# Sheet5.net
KiCad netlist of a schematic drawn in Altium Designer
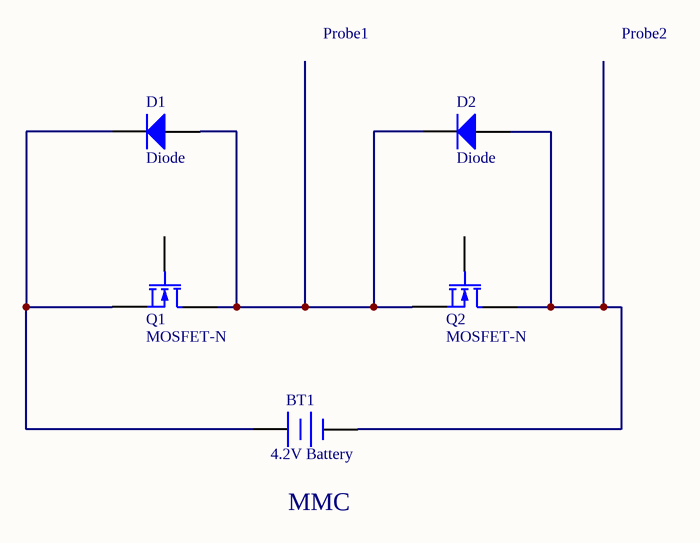
[diagram p0: Sheet5.SchDoc]

(export (version "E")
  (design (tool "Eeschema 10.0.6"))
  (components
    (comp (ref "BT1")
      (value "4.2V Battery")
      (footprint "BAT-2")
      (description "Multicell Battery")
      (fields (field (name "PUBLISHER") "Altium Limited"))
      (libsource (lib "Miscellaneous Devices") (part "Battery"))
    )
    (comp (ref "D1")
      (value "Diode")
      (footprint "SMC")
      (description "Default Diode")
      (fields (field (name "PUBLISHER") "Altium Limited"))
      (libsource (lib "Miscellaneous Devices") (part "Diode"))
    )
    (comp (ref "D2")
      (value "Diode")
      (footprint "SMC")
      (description "Default Diode")
      (fields (field (name "PUBLISHER") "Altium Limited"))
      (libsource (lib "Miscellaneous Devices") (part "Diode"))
    )
    (comp (ref "Q1")
      (value "MOSFET-N")
      (footprint "E3")
      (description "N-Channel MOSFET")
      (fields (field (name "PUBLISHER") "Altium Limited"))
      (libsource (lib "Miscellaneous Devices") (part "MOSFET-N"))
    )
    (comp (ref "Q2")
      (value "MOSFET-N")
      (footprint "E3")
      (description "N-Channel MOSFET")
      (fields (field (name "PUBLISHER") "Altium Limited"))
      (libsource (lib "Miscellaneous Devices") (part "MOSFET-N"))
    )
  )
  (nets
    (net (code "1") (name "Net-(BT1-+)") (class "Default")
      (node (ref "BT1") (pin "1") (pinfunction "+_1") (pintype "passive"))
      (node (ref "D1") (pin "2") (pinfunction "K_2") (pintype "passive"))
      (node (ref "Q1") (pin "3") (pinfunction "S_3") (pintype "passive"))
    )
    (net (code "2") (name "Net-(BT1--)") (class "Default")
      (node (ref "BT1") (pin "2") (pinfunction "-_2") (pintype "passive"))
      (node (ref "D2") (pin "1") (pinfunction "A_1") (pintype "passive"))
      (node (ref "Q2") (pin "1") (pinfunction "D_1") (pintype "passive"))
    )
    (net (code "3") (name "Net-(D1-A)") (class "Default")
      (node (ref "D1") (pin "1") (pinfunction "A_1") (pintype "passive"))
      (node (ref "D2") (pin "2") (pinfunction "K_2") (pintype "passive"))
      (node (ref "Q1") (pin "1") (pinfunction "D_1") (pintype "passive"))
      (node (ref "Q2") (pin "3") (pinfunction "S_3") (pintype "passive"))
    )
    (net (code "4") (name "unconnected-(Q1-G-Pad2)") (class "Default")
      (node (ref "Q1") (pin "2") (pinfunction "G_2") (pintype "passive"))
    )
    (net (code "5") (name "unconnected-(Q2-G-Pad2)") (class "Default")
      (node (ref "Q2") (pin "2") (pinfunction "G_2") (pintype "passive"))
    )
  )
)
